# Payload_Switch_Board.net
KiCad netlist of a schematic drawn in Altium Designer
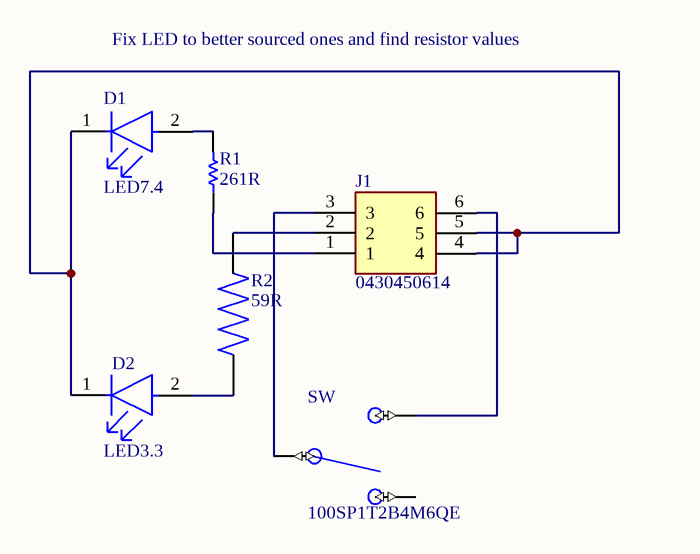
[diagram p0: Payload_Switch_Board.SchDoc]

(export (version "E")
  (design (tool "Eeschema 10.0.6"))
  (components
    (comp (ref "D1")
      (value "LED7.4")
      (footprint "FP-APHHS1005CGCK-MFG")
      (description "LED GREEN CLEAR CHIP SMD")
      (libsource (lib "Altium Content Vault") (part "8706943c75ba83719d021d2fdc84c58"))
    )
    (comp (ref "D2")
      (value "LED3.3")
      (footprint "FP-APHHS1005CGCK-MFG")
      (description "LED GREEN CLEAR CHIP SMD")
      (libsource (lib "Altium Content Vault") (part "8706943c75ba83719d021d2fdc84c58"))
    )
    (comp (ref "J1")
      (value "0430450614")
      (footprint "SamacSys:0430450614")
      (description "Connector")
      (libsource (lib "*") (part "0430450614"))
    )
    (comp (ref "R1")
      (value "261R")
      (footprint "RESC3216X70X50NL05T20")
      (fields (field (name "MANUFACTURER") "Panasonic") (field (name "PART NUMBER") "ERJ-8ENF2610V"))
      (libsource (lib "Altium Content Vault") (part "RES"))
    )
    (comp (ref "R2")
      (value "59R")
      (footprint "RES_ERJP06F59R0V")
      (fields (field (name "MP") "ERJP06F59R0V"))
      (libsource (lib "ERJP06F59R0V") (part "ERJP06F59R0V"))
    )
    (comp (ref "SW")
      (value "100SP1T2B4M6QE")
      (footprint "TOGGLE_RA")
      (description "Toggle Switch SPDT Through Hole, Right Angle")
      (fields (field (name "MF") "E-Switch"))
      (libsource (lib "100SP1T2B4M6QE") (part "100SP1T2B4M6QE"))
    )
  )
  (nets
    (net (code "1") (name "Net-(D1-A)") (class "Default")
      (node (ref "D1") (pin "2") (pinfunction "A_2") (pintype "passive"))
      (node (ref "R1") (pin "2") (pinfunction "2_2") (pintype "passive"))
    )
    (net (code "2") (name "Net-(D1-C)") (class "Default")
      (node (ref "D1") (pin "1") (pinfunction "C_1") (pintype "passive"))
      (node (ref "D2") (pin "1") (pinfunction "C_1") (pintype "passive"))
      (node (ref "J1") (pin "4") (pinfunction "4_4") (pintype "passive"))
      (node (ref "J1") (pin "5") (pinfunction "5_5") (pintype "passive"))
    )
    (net (code "3") (name "Net-(D2-A)") (class "Default")
      (node (ref "D2") (pin "2") (pinfunction "A_2") (pintype "passive"))
      (node (ref "R2") (pin "1") (pinfunction "1_1") (pintype "passive"))
    )
    (net (code "4") (name "Net-(J1-Pad1)") (class "Default")
      (node (ref "J1") (pin "1") (pinfunction "1_1") (pintype "passive"))
      (node (ref "R1") (pin "1") (pinfunction "1_1") (pintype "passive"))
    )
    (net (code "5") (name "Net-(J1-Pad2)") (class "Default")
      (node (ref "J1") (pin "2") (pinfunction "2_2") (pintype "passive"))
      (node (ref "R2") (pin "2") (pinfunction "2_2") (pintype "passive"))
    )
    (net (code "6") (name "Net-(SW-COM)") (class "Default")
      (node (ref "J1") (pin "3") (pinfunction "3_3") (pintype "passive"))
      (node (ref "SW") (pin "2") (pinfunction "COM_2") (pintype "bidirectional"))
    )
    (net (code "7") (name "Net-(SW-P$2)") (class "Default")
      (node (ref "J1") (pin "6") (pinfunction "6_6") (pintype "passive"))
      (node (ref "SW") (pin "1") (pinfunction "P$2_1") (pintype "bidirectional"))
    )
    (net (code "8") (name "unconnected-(SW-P$3-Pad3)") (class "Default")
      (node (ref "SW") (pin "3") (pinfunction "P$3_3") (pintype "bidirectional"))
    )
  )
)
